# CanCom_Sch.net
KiCad netlist of a schematic drawn in Altium Designer
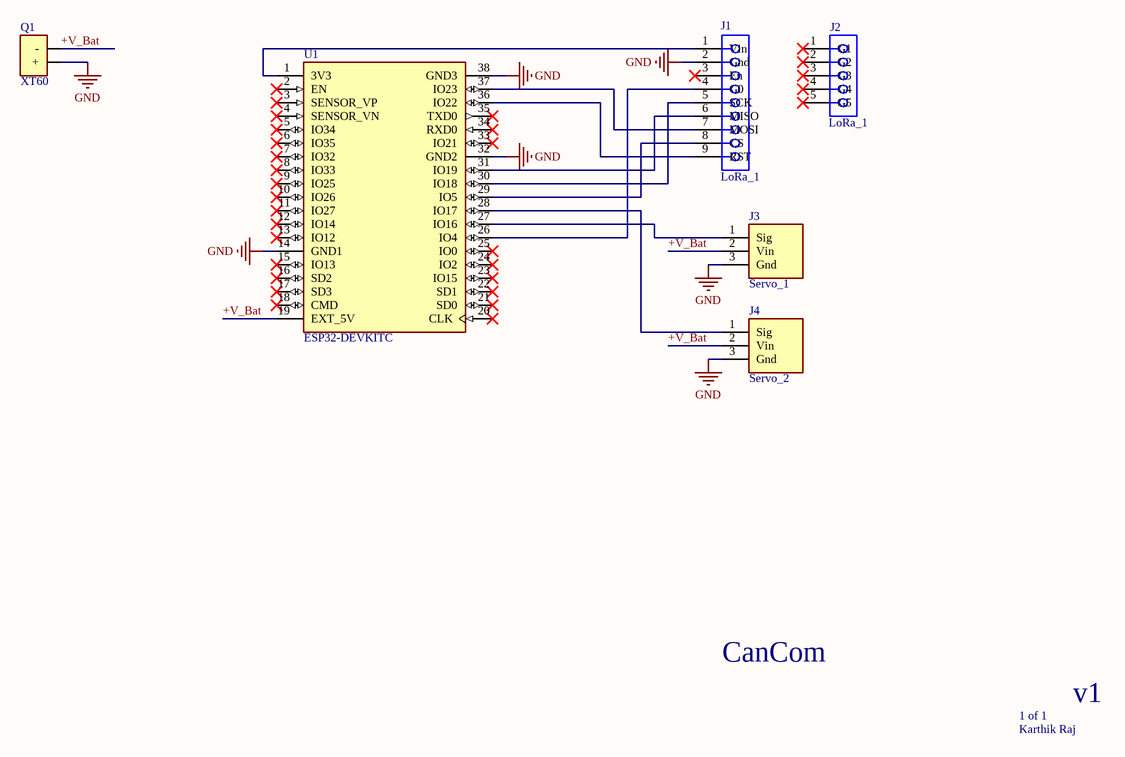
[diagram p0: CanCom_Sch.SchDoc]

(export (version "E")
  (design (tool "Eeschema 10.0.6"))
  (components
    (comp (ref "J1")
      (value "LoRa_1")
      (footprint "61300911821")
      (libsource (lib "Altium Content Vault") (part "Header_Female_1R_09P"))
    )
    (comp (ref "J2")
      (value "LoRa_1")
      (footprint "61300511821")
      (libsource (lib "Altium Content Vault") (part "Header_Female_1R_05P"))
    )
    (comp (ref "J3")
      (value "Servo_1")
      (footprint "TE_87220-3")
      (description "Header; Standard; PC Board; Single; 3; 0.025 in.; 0.125 in.; Square; 0.1 in.")
      (fields (field (name "MP") "87220-3") (field (name "MF") "TE Connectivity"))
      (libsource (lib "NTU") (part "87220-3"))
    )
    (comp (ref "J4")
      (value "Servo_2")
      (footprint "TE_87220-3")
      (description "Header; Standard; PC Board; Single; 3; 0.025 in.; 0.125 in.; Square; 0.1 in.")
      (fields (field (name "MP") "87220-3") (field (name "MF") "TE Connectivity"))
      (libsource (lib "NTU") (part "87220-3"))
    )
    (comp (ref "Q1")
      (value "XT60")
      (footprint "AMASS_XT60PB-M")
      (description "Power connector; 65A; PIN: 2; Colour: yellow")
      (fields (field (name "MP") "XT60 YELLOW") (field (name "MF") "Pololu"))
      (libsource (lib "NTU") (part "XT60_YELLOW"))
    )
    (comp (ref "U1")
      (value "ESP32-DEVKITC")
      (footprint "MODULE_ESP32-DEVKITC")
      (fields (field (name "MF") "Espressif Systems"))
      (libsource (lib "NTU") (part "ESP32-DEVKITC"))
    )
  )
  (nets
    (net (code "1") (name "/+V_Bat") (class "Default")
      (node (ref "J3") (pin "2") (pinfunction "Vin_2") (pintype "passive"))
      (node (ref "J4") (pin "2") (pinfunction "Vin_2") (pintype "passive"))
      (node (ref "Q1") (pin "2") (pinfunction "-_2") (pintype "passive"))
      (node (ref "U1") (pin "19") (pinfunction "EXT_5V_19") (pintype "power_in"))
    )
    (net (code "2") (name "GND") (class "Default")
      (node (ref "J1") (pin "2") (pinfunction "Gnd_2") (pintype "passive"))
      (node (ref "J3") (pin "3") (pinfunction "Gnd_3") (pintype "passive"))
      (node (ref "J4") (pin "3") (pinfunction "Gnd_3") (pintype "passive"))
      (node (ref "Q1") (pin "1") (pinfunction "+_1") (pintype "passive"))
      (node (ref "U1") (pin "14") (pinfunction "GND1_14") (pintype "power_in"))
      (node (ref "U1") (pin "32") (pinfunction "GND2_32") (pintype "power_in"))
      (node (ref "U1") (pin "38") (pinfunction "GND3_38") (pintype "power_in"))
    )
    (net (code "3") (name "Net-(J1-CS)") (class "Default")
      (node (ref "J1") (pin "8") (pinfunction "CS_8") (pintype "passive"))
      (node (ref "U1") (pin "29") (pinfunction "IO5_29") (pintype "bidirectional"))
    )
    (net (code "4") (name "Net-(J1-G0)") (class "Default")
      (node (ref "J1") (pin "4") (pinfunction "G0_4") (pintype "passive"))
      (node (ref "U1") (pin "26") (pinfunction "IO4_26") (pintype "bidirectional"))
    )
    (net (code "5") (name "Net-(J1-MISO)") (class "Default")
      (node (ref "J1") (pin "6") (pinfunction "MISO_6") (pintype "passive"))
      (node (ref "U1") (pin "31") (pinfunction "IO19_31") (pintype "bidirectional"))
    )
    (net (code "6") (name "Net-(J1-MOSI)") (class "Default")
      (node (ref "J1") (pin "7") (pinfunction "MOSI_7") (pintype "passive"))
      (node (ref "U1") (pin "37") (pinfunction "IO23_37") (pintype "bidirectional"))
    )
    (net (code "7") (name "Net-(J1-RST)") (class "Default")
      (node (ref "J1") (pin "9") (pinfunction "RST_9") (pintype "passive"))
      (node (ref "U1") (pin "36") (pinfunction "IO22_36") (pintype "bidirectional"))
    )
    (net (code "8") (name "Net-(J1-SCK)") (class "Default")
      (node (ref "J1") (pin "5") (pinfunction "SCK_5") (pintype "passive"))
      (node (ref "U1") (pin "30") (pinfunction "IO18_30") (pintype "bidirectional"))
    )
    (net (code "9") (name "Net-(J1-Vin)") (class "Default")
      (node (ref "J1") (pin "1") (pinfunction "Vin_1") (pintype "passive"))
      (node (ref "U1") (pin "1") (pinfunction "3V3_1") (pintype "power_in"))
    )
    (net (code "10") (name "Net-(J3-Sig)") (class "Default")
      (node (ref "J3") (pin "1") (pinfunction "Sig_1") (pintype "passive"))
      (node (ref "U1") (pin "27") (pinfunction "IO16_27") (pintype "bidirectional"))
    )
    (net (code "11") (name "Net-(J4-Sig)") (class "Default")
      (node (ref "J4") (pin "1") (pinfunction "Sig_1") (pintype "passive"))
      (node (ref "U1") (pin "28") (pinfunction "IO17_28") (pintype "bidirectional"))
    )
    (net (code "12") (name "unconnected-(J1-En-Pad3)") (class "Default")
      (node (ref "J1") (pin "3") (pinfunction "En_3") (pintype "passive+no_connect"))
    )
    (net (code "13") (name "unconnected-(J2-G1-Pad1)") (class "Default")
      (node (ref "J2") (pin "1") (pinfunction "G1_1") (pintype "passive+no_connect"))
    )
    (net (code "14") (name "unconnected-(J2-G2-Pad2)") (class "Default")
      (node (ref "J2") (pin "2") (pinfunction "G2_2") (pintype "passive+no_connect"))
    )
    (net (code "15") (name "unconnected-(J2-G3-Pad3)") (class "Default")
      (node (ref "J2") (pin "3") (pinfunction "G3_3") (pintype "passive+no_connect"))
    )
    (net (code "16") (name "unconnected-(J2-G4-Pad4)") (class "Default")
      (node (ref "J2") (pin "4") (pinfunction "G4_4") (pintype "passive+no_connect"))
    )
    (net (code "17") (name "unconnected-(J2-G5-Pad5)") (class "Default")
      (node (ref "J2") (pin "5") (pinfunction "G5_5") (pintype "passive+no_connect"))
    )
    (net (code "18") (name "unconnected-(U1-CLK-Pad20)") (class "Default")
      (node (ref "U1") (pin "20") (pinfunction "CLK_20") (pintype "input+no_connect"))
    )
    (net (code "19") (name "unconnected-(U1-CMD-Pad18)") (class "Default")
      (node (ref "U1") (pin "18") (pinfunction "CMD_18") (pintype "bidirectional+no_connect"))
    )
    (net (code "20") (name "unconnected-(U1-EN-Pad2)") (class "Default")
      (node (ref "U1") (pin "2") (pinfunction "EN_2") (pintype "input+no_connect"))
    )
    (net (code "21") (name "unconnected-(U1-IO0-Pad25)") (class "Default")
      (node (ref "U1") (pin "25") (pinfunction "IO0_25") (pintype "bidirectional+no_connect"))
    )
    (net (code "22") (name "unconnected-(U1-IO2-Pad24)") (class "Default")
      (node (ref "U1") (pin "24") (pinfunction "IO2_24") (pintype "bidirectional+no_connect"))
    )
    (net (code "23") (name "unconnected-(U1-IO12-Pad13)") (class "Default")
      (node (ref "U1") (pin "13") (pinfunction "IO12_13") (pintype "bidirectional+no_connect"))
    )
    (net (code "24") (name "unconnected-(U1-IO13-Pad15)") (class "Default")
      (node (ref "U1") (pin "15") (pinfunction "IO13_15") (pintype "bidirectional+no_connect"))
    )
    (net (code "25") (name "unconnected-(U1-IO14-Pad12)") (class "Default")
      (node (ref "U1") (pin "12") (pinfunction "IO14_12") (pintype "bidirectional+no_connect"))
    )
    (net (code "26") (name "unconnected-(U1-IO15-Pad23)") (class "Default")
      (node (ref "U1") (pin "23") (pinfunction "IO15_23") (pintype "bidirectional+no_connect"))
    )
    (net (code "27") (name "unconnected-(U1-IO21-Pad33)") (class "Default")
      (node (ref "U1") (pin "33") (pinfunction "IO21_33") (pintype "bidirectional+no_connect"))
    )
    (net (code "28") (name "unconnected-(U1-IO25-Pad9)") (class "Default")
      (node (ref "U1") (pin "9") (pinfunction "IO25_9") (pintype "bidirectional+no_connect"))
    )
    (net (code "29") (name "unconnected-(U1-IO26-Pad10)") (class "Default")
      (node (ref "U1") (pin "10") (pinfunction "IO26_10") (pintype "bidirectional+no_connect"))
    )
    (net (code "30") (name "unconnected-(U1-IO27-Pad11)") (class "Default")
      (node (ref "U1") (pin "11") (pinfunction "IO27_11") (pintype "bidirectional+no_connect"))
    )
    (net (code "31") (name "unconnected-(U1-IO32-Pad7)") (class "Default")
      (node (ref "U1") (pin "7") (pinfunction "IO32_7") (pintype "bidirectional+no_connect"))
    )
    (net (code "32") (name "unconnected-(U1-IO33-Pad8)") (class "Default")
      (node (ref "U1") (pin "8") (pinfunction "IO33_8") (pintype "bidirectional+no_connect"))
    )
    (net (code "33") (name "unconnected-(U1-IO34-Pad5)") (class "Default")
      (node (ref "U1") (pin "5") (pinfunction "IO34_5") (pintype "bidirectional+no_connect"))
    )
    (net (code "34") (name "unconnected-(U1-IO35-Pad6)") (class "Default")
      (node (ref "U1") (pin "6") (pinfunction "IO35_6") (pintype "bidirectional+no_connect"))
    )
    (net (code "35") (name "unconnected-(U1-RXD0-Pad34)") (class "Default")
      (node (ref "U1") (pin "34") (pinfunction "RXD0_34") (pintype "input+no_connect"))
    )
    (net (code "36") (name "unconnected-(U1-SD0-Pad21)") (class "Default")
      (node (ref "U1") (pin "21") (pinfunction "SD0_21") (pintype "bidirectional+no_connect"))
    )
    (net (code "37") (name "unconnected-(U1-SD1-Pad22)") (class "Default")
      (node (ref "U1") (pin "22") (pinfunction "SD1_22") (pintype "bidirectional+no_connect"))
    )
    (net (code "38") (name "unconnected-(U1-SD2-Pad16)") (class "Default")
      (node (ref "U1") (pin "16") (pinfunction "SD2_16") (pintype "bidirectional+no_connect"))
    )
    (net (code "39") (name "unconnected-(U1-SD3-Pad17)") (class "Default")
      (node (ref "U1") (pin "17") (pinfunction "SD3_17") (pintype "bidirectional+no_connect"))
    )
    (net (code "40") (name "unconnected-(U1-SENSOR_VN-Pad4)") (class "Default")
      (node (ref "U1") (pin "4") (pinfunction "SENSOR_VN_4") (pintype "input+no_connect"))
    )
    (net (code "41") (name "unconnected-(U1-SENSOR_VP-Pad3)") (class "Default")
      (node (ref "U1") (pin "3") (pinfunction "SENSOR_VP_3") (pintype "input+no_connect"))
    )
    (net (code "42") (name "unconnected-(U1-TXD0-Pad35)") (class "Default")
      (node (ref "U1") (pin "35") (pinfunction "TXD0_35") (pintype "output+no_connect"))
    )
  )
)
